# bqcreative_v2.net
KiCad netlist of a schematic drawn in EAGLE
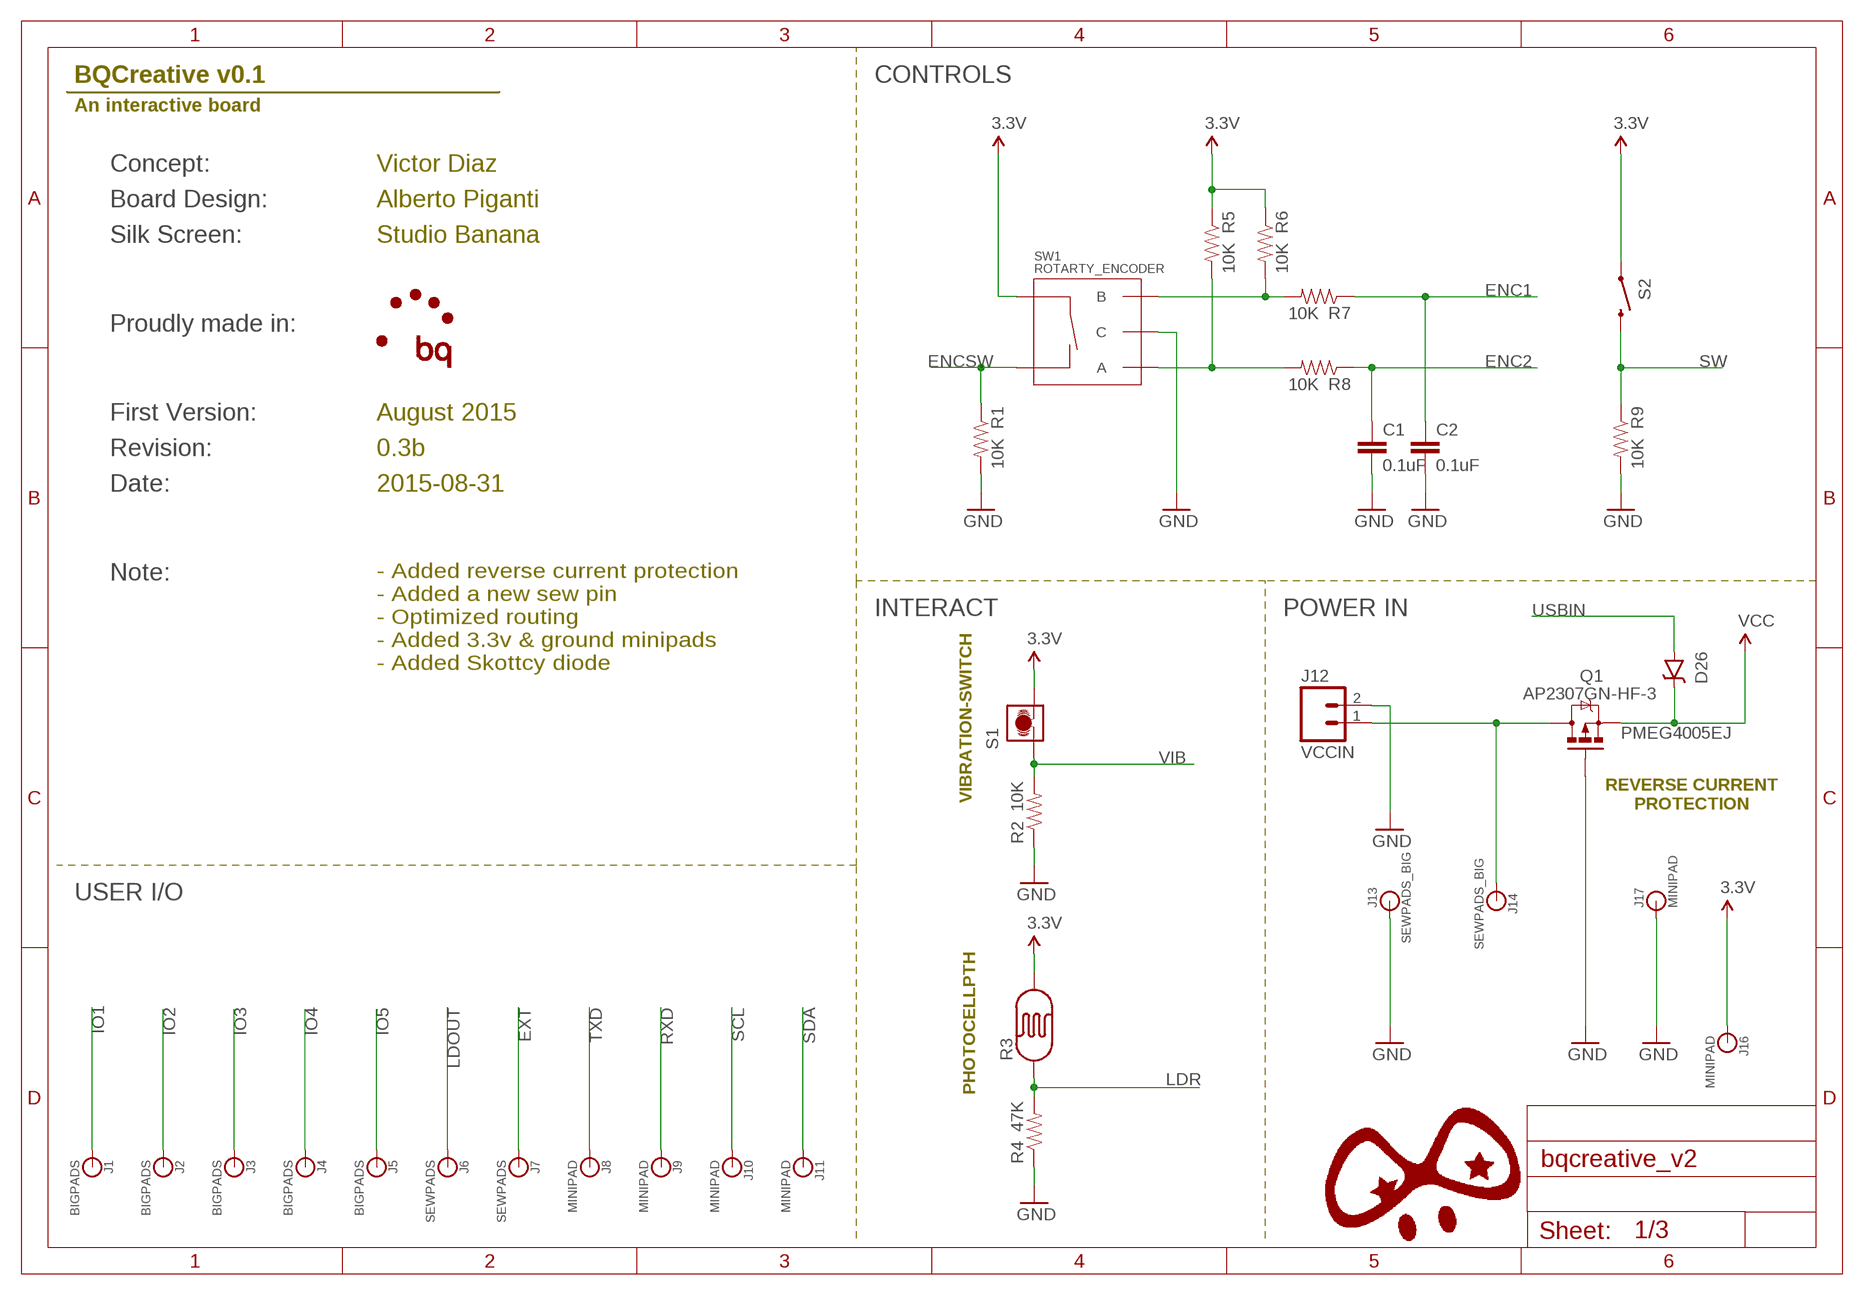
[diagram p0: schematic, sheet 1]
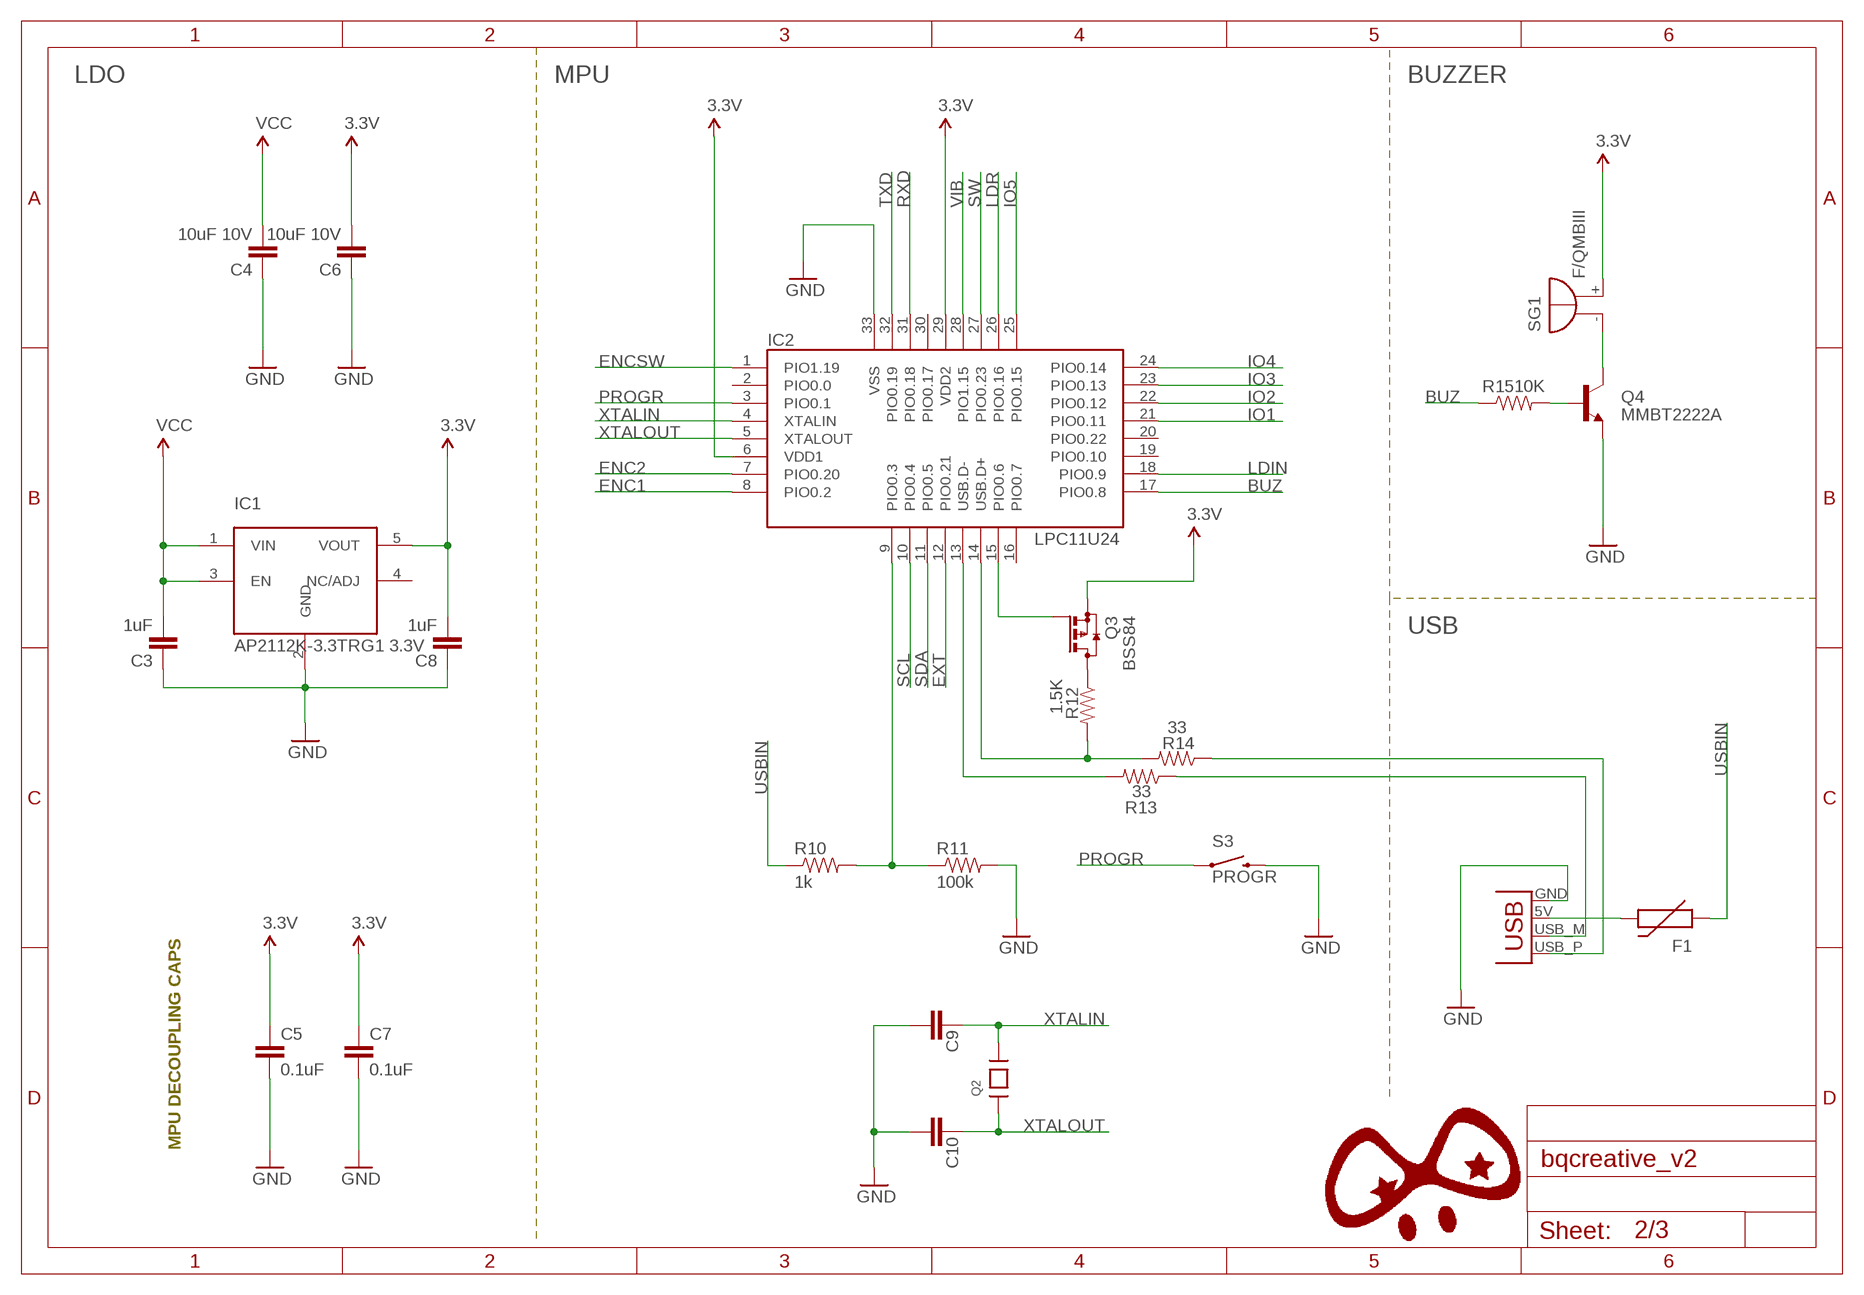
[diagram p1: schematic, sheet 2]
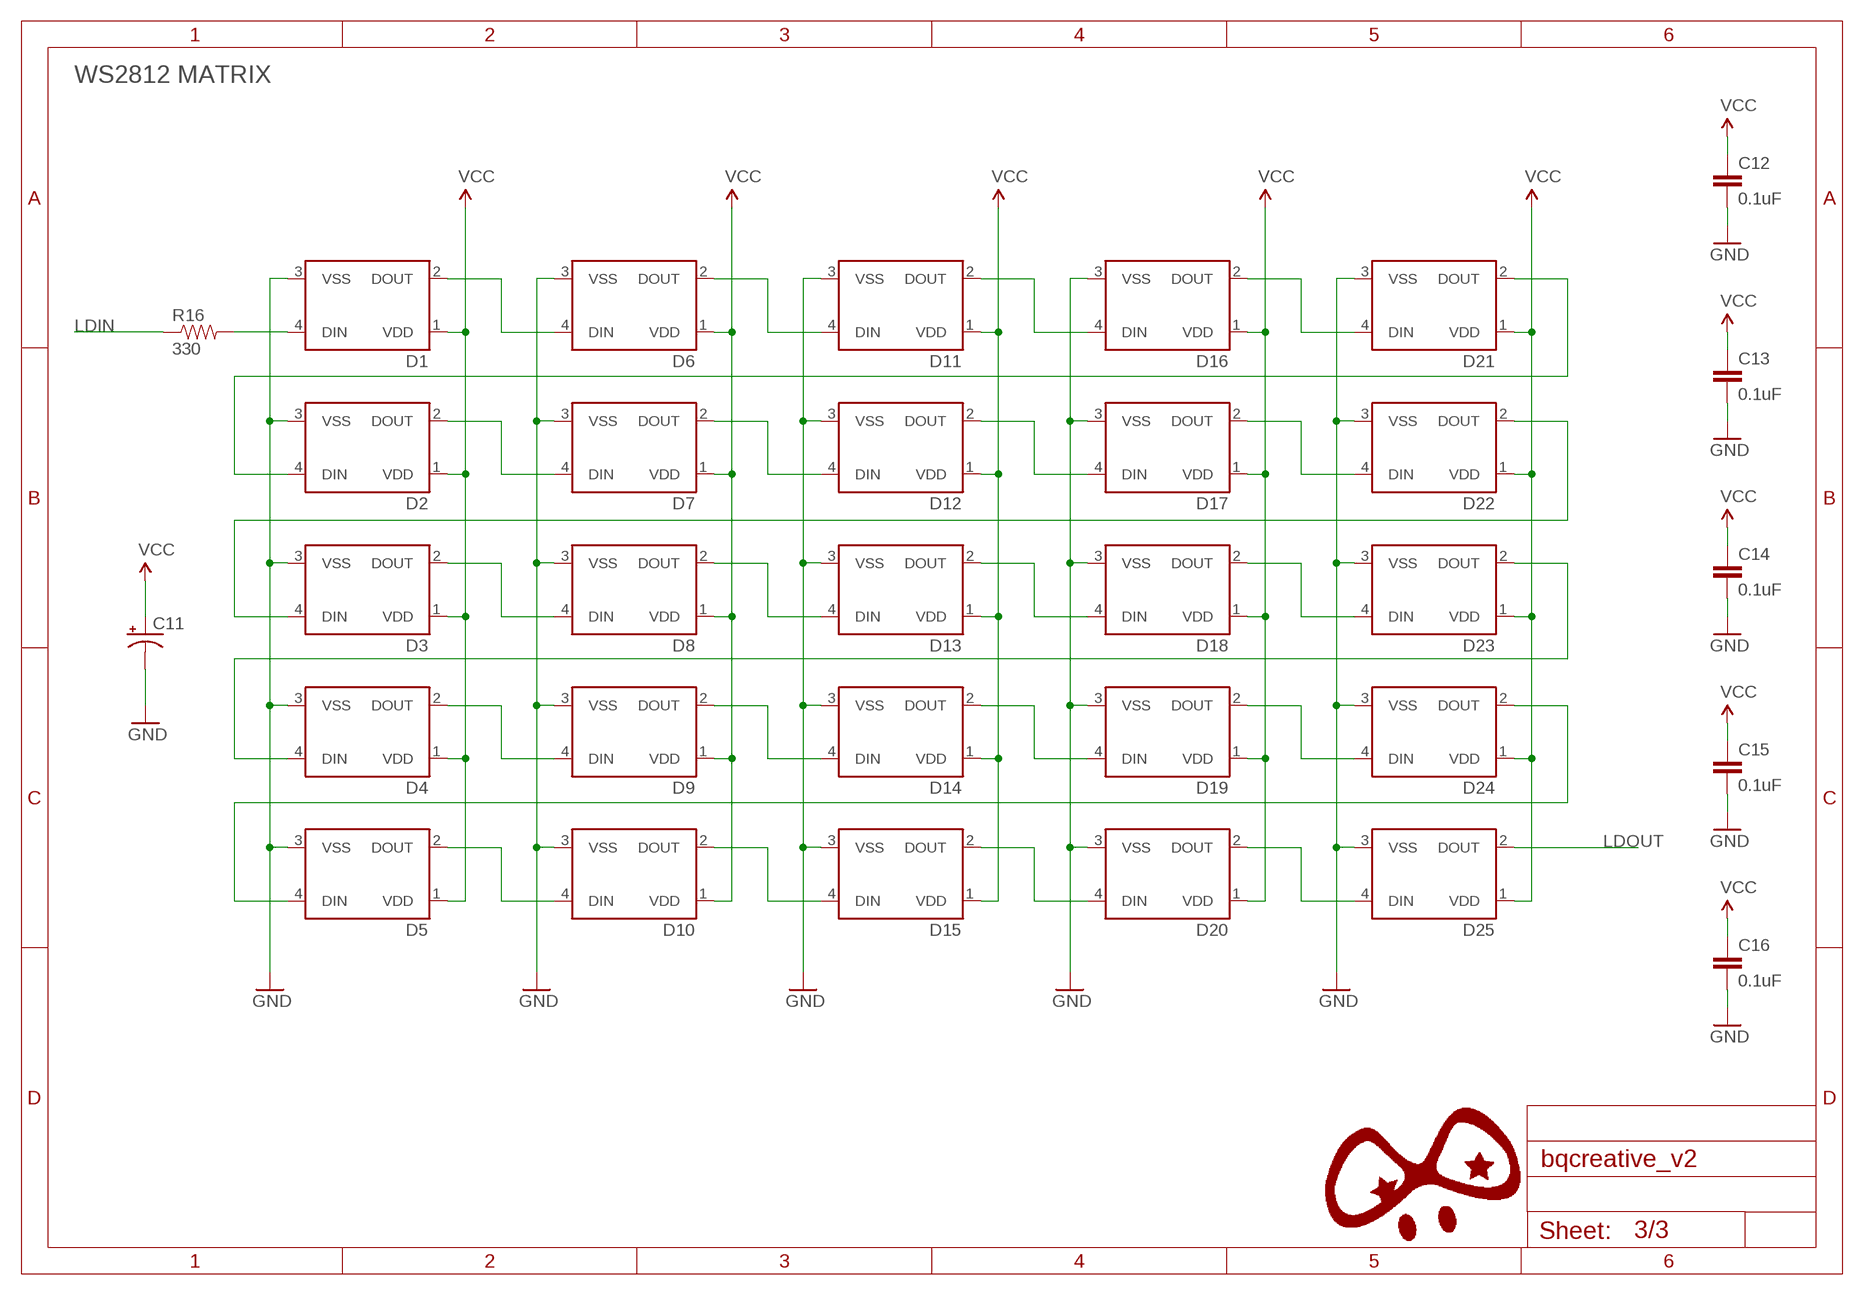
[diagram p2: schematic, sheet 3]

(export (version "E")
  (design (tool "Eeschema 10.0.6"))
  (components
    (comp (ref "C3")
      (value "1uF")
      (footprint "eagle-import:0402-CAP")
      (libsource (lib "eagle-import") (part "SparkFun-Passives_CAP0402-CAP"))
    )
    (comp (ref "C4")
      (value "10uF 10V")
      (footprint "eagle-import:0402-CAP")
      (libsource (lib "eagle-import") (part "SparkFun-Passives_CAP0402-CAP"))
    )
    (comp (ref "C5")
      (value "0.1uF")
      (footprint "eagle-import:0402-CAP")
      (libsource (lib "eagle-import") (part "SparkFun-Passives_CAP0402-CAP"))
    )
    (comp (ref "C6")
      (value "10uF 10V")
      (footprint "eagle-import:0402-CAP")
      (libsource (lib "eagle-import") (part "SparkFun-Passives_CAP0402-CAP"))
    )
    (comp (ref "C7")
      (value "0.1uF")
      (footprint "eagle-import:0402-CAP")
      (libsource (lib "eagle-import") (part "SparkFun-Passives_CAP0402-CAP"))
    )
    (comp (ref "C8")
      (value "1uF")
      (footprint "eagle-import:0402-CAP")
      (libsource (lib "eagle-import") (part "SparkFun-Passives_CAP0402-CAP"))
    )
    (comp (ref "C9")
      (value "27pF")
      (footprint "eagle-import:0402-CAP")
      (libsource (lib "eagle-import") (part "SparkFun-Passives_CAP0402-CAP"))
    )
    (comp (ref "C10")
      (value "27pF")
      (footprint "eagle-import:0402-CAP")
      (libsource (lib "eagle-import") (part "SparkFun-Passives_CAP0402-CAP"))
    )
    (comp (ref "F1")
      (value "PTC0603")
      (footprint "eagle-import:0603")
      (libsource (lib "eagle-import") (part "PTC0603"))
    )
    (comp (ref "IC1")
      (value "AP2112K-3.3TRG1 3.3V")
      (footprint "eagle-import:SOT23-5")
      (libsource (lib "eagle-import") (part "5PIN_REG"))
    )
    (comp (ref "IC2")
      (value "LPC11U24")
      (footprint "eagle-import:HVQFN33_5X5MM")
      (libsource (lib "eagle-import") (part "LPC11U2X_HVQFN33(5X5)"))
    )
    (comp (ref "J15")
      (value "USBPCB")
      (footprint "eagle-import:USB-A-PCB")
      (libsource (lib "eagle-import") (part "USBPCB"))
    )
    (comp (ref "Q2")
      (value "12MHz 4 pad crystal 3.2x2.5")
      (footprint "eagle-import:CRYSTAL_3.2X2.5")
      (libsource (lib "eagle-import") (part "CRYSTAL3.2X2.5"))
    )
    (comp (ref "Q3")
      (value "BSS84")
      (footprint "eagle-import:SOT23")
      (libsource (lib "eagle-import") (part "BSS84"))
    )
    (comp (ref "Q4")
      (value "MMBT2222A")
      (footprint "eagle-import:SOT23-3")
      (libsource (lib "eagle-import") (part "TRANSISTOR_NPNMMBT2222A"))
    )
    (comp (ref "R10")
      (value "1k")
      (footprint "eagle-import:0402-RES")
      (libsource (lib "eagle-import") (part "SparkFun-Passives_RESISTOR0402-RES"))
    )
    (comp (ref "R11")
      (value "100k")
      (footprint "eagle-import:0402-RES")
      (libsource (lib "eagle-import") (part "SparkFun-Passives_RESISTOR0402-RES"))
    )
    (comp (ref "R12")
      (value "1.5K")
      (footprint "eagle-import:0402-RES")
      (libsource (lib "eagle-import") (part "SparkFun-Passives_RESISTOR0402-RES"))
    )
    (comp (ref "R13")
      (value "33")
      (footprint "eagle-import:0402-RES")
      (libsource (lib "eagle-import") (part "SparkFun-Passives_RESISTOR0402-RES"))
    )
    (comp (ref "R14")
      (value "33")
      (footprint "eagle-import:0402-RES")
      (libsource (lib "eagle-import") (part "SparkFun-Passives_RESISTOR0402-RES"))
    )
    (comp (ref "R15")
      (value "10K")
      (footprint "eagle-import:0402-RES")
      (libsource (lib "eagle-import") (part "RESISTOR0402-RES"))
    )
    (comp (ref "S3")
      (value "PROGR")
      (footprint "eagle-import:TACTILE-SWITCH-1101NE")
      (libsource (lib "eagle-import") (part "SWITCH-MOMENTARY-2SMD-1101NE"))
    )
    (comp (ref "SG1")
      (value "F/QMBIII")
      (footprint "eagle-import:F_QMBIII")
      (libsource (lib "eagle-import") (part "F/QMBIII"))
    )
    (comp (ref "C11")
      (value "CAP_POL1206")
      (footprint "eagle-import:EIA3216")
      (libsource (lib "eagle-import") (part "CAP_POL1206"))
    )
    (comp (ref "C12")
      (value "0.1uF")
      (footprint "eagle-import:0402-CAP")
      (libsource (lib "eagle-import") (part "SparkFun-Passives_CAP0402-CAP"))
    )
    (comp (ref "C13")
      (value "0.1uF")
      (footprint "eagle-import:0402-CAP")
      (libsource (lib "eagle-import") (part "SparkFun-Passives_CAP0402-CAP"))
    )
    (comp (ref "C14")
      (value "0.1uF")
      (footprint "eagle-import:0402-CAP")
      (libsource (lib "eagle-import") (part "SparkFun-Passives_CAP0402-CAP"))
    )
    (comp (ref "C15")
      (value "0.1uF")
      (footprint "eagle-import:0402-CAP")
      (libsource (lib "eagle-import") (part "SparkFun-Passives_CAP0402-CAP"))
    )
    (comp (ref "C16")
      (value "0.1uF")
      (footprint "eagle-import:0402-CAP")
      (libsource (lib "eagle-import") (part "SparkFun-Passives_CAP0402-CAP"))
    )
    (comp (ref "D1")
      (value "WS2812B")
      (footprint "eagle-import:WS2812B")
      (libsource (lib "eagle-import") (part "WS2812B"))
    )
    (comp (ref "D2")
      (value "WS2812B")
      (footprint "eagle-import:WS2812B")
      (libsource (lib "eagle-import") (part "WS2812B"))
    )
    (comp (ref "D3")
      (value "WS2812B")
      (footprint "eagle-import:WS2812B")
      (libsource (lib "eagle-import") (part "WS2812B"))
    )
    (comp (ref "D4")
      (value "WS2812B")
      (footprint "eagle-import:WS2812B")
      (libsource (lib "eagle-import") (part "WS2812B"))
    )
    (comp (ref "D5")
      (value "WS2812B")
      (footprint "eagle-import:WS2812B")
      (libsource (lib "eagle-import") (part "WS2812B"))
    )
    (comp (ref "D6")
      (value "WS2812B")
      (footprint "eagle-import:WS2812B")
      (libsource (lib "eagle-import") (part "WS2812B"))
    )
    (comp (ref "D7")
      (value "WS2812B")
      (footprint "eagle-import:WS2812B")
      (libsource (lib "eagle-import") (part "WS2812B"))
    )
    (comp (ref "D8")
      (value "WS2812B")
      (footprint "eagle-import:WS2812B")
      (libsource (lib "eagle-import") (part "WS2812B"))
    )
    (comp (ref "D9")
      (value "WS2812B")
      (footprint "eagle-import:WS2812B")
      (libsource (lib "eagle-import") (part "WS2812B"))
    )
    (comp (ref "D10")
      (value "WS2812B")
      (footprint "eagle-import:WS2812B")
      (libsource (lib "eagle-import") (part "WS2812B"))
    )
    (comp (ref "D11")
      (value "WS2812B")
      (footprint "eagle-import:WS2812B")
      (libsource (lib "eagle-import") (part "WS2812B"))
    )
    (comp (ref "D12")
      (value "WS2812B")
      (footprint "eagle-import:WS2812B")
      (libsource (lib "eagle-import") (part "WS2812B"))
    )
    (comp (ref "D13")
      (value "WS2812B")
      (footprint "eagle-import:WS2812B")
      (libsource (lib "eagle-import") (part "WS2812B"))
    )
    (comp (ref "D14")
      (value "WS2812B")
      (footprint "eagle-import:WS2812B")
      (libsource (lib "eagle-import") (part "WS2812B"))
    )
    (comp (ref "D15")
      (value "WS2812B")
      (footprint "eagle-import:WS2812B")
      (libsource (lib "eagle-import") (part "WS2812B"))
    )
    (comp (ref "D16")
      (value "WS2812B")
      (footprint "eagle-import:WS2812B")
      (libsource (lib "eagle-import") (part "WS2812B"))
    )
    (comp (ref "D17")
      (value "WS2812B")
      (footprint "eagle-import:WS2812B")
      (libsource (lib "eagle-import") (part "WS2812B"))
    )
    (comp (ref "D18")
      (value "WS2812B")
      (footprint "eagle-import:WS2812B")
      (libsource (lib "eagle-import") (part "WS2812B"))
    )
    (comp (ref "D19")
      (value "WS2812B")
      (footprint "eagle-import:WS2812B")
      (libsource (lib "eagle-import") (part "WS2812B"))
    )
    (comp (ref "D20")
      (value "WS2812B")
      (footprint "eagle-import:WS2812B")
      (libsource (lib "eagle-import") (part "WS2812B"))
    )
    (comp (ref "D21")
      (value "WS2812B")
      (footprint "eagle-import:WS2812B")
      (libsource (lib "eagle-import") (part "WS2812B"))
    )
    (comp (ref "D22")
      (value "WS2812B")
      (footprint "eagle-import:WS2812B")
      (libsource (lib "eagle-import") (part "WS2812B"))
    )
    (comp (ref "D23")
      (value "WS2812B")
      (footprint "eagle-import:WS2812B")
      (libsource (lib "eagle-import") (part "WS2812B"))
    )
    (comp (ref "D24")
      (value "WS2812B")
      (footprint "eagle-import:WS2812B")
      (libsource (lib "eagle-import") (part "WS2812B"))
    )
    (comp (ref "D25")
      (value "WS2812B")
      (footprint "eagle-import:WS2812B")
      (libsource (lib "eagle-import") (part "WS2812B"))
    )
    (comp (ref "R16")
      (value "330")
      (footprint "eagle-import:0402-RES")
      (libsource (lib "eagle-import") (part "SparkFun-Passives_RESISTOR0402-RES"))
    )
    (comp (ref "C1")
      (value "0.1uF")
      (footprint "eagle-import:0603-CAP")
      (libsource (lib "eagle-import") (part "CAP0603-CAP"))
    )
    (comp (ref "C2")
      (value "0.1uF")
      (footprint "eagle-import:0603-CAP")
      (libsource (lib "eagle-import") (part "CAP0603-CAP"))
    )
    (comp (ref "D26")
      (value "PMEG4005EJ")
      (footprint "eagle-import:SOD-323")
      (libsource (lib "eagle-import") (part "DIODE-SCHOTTKY-PMEG4005EJ"))
    )
    (comp (ref "J1")
      (value "BIGPADS")
      (footprint "eagle-import:BIGPAD")
      (libsource (lib "eagle-import") (part "BIGPADS"))
    )
    (comp (ref "J2")
      (value "BIGPADS")
      (footprint "eagle-import:BIGPAD")
      (libsource (lib "eagle-import") (part "BIGPADS"))
    )
    (comp (ref "J3")
      (value "BIGPADS")
      (footprint "eagle-import:BIGPAD")
      (libsource (lib "eagle-import") (part "BIGPADS"))
    )
    (comp (ref "J4")
      (value "BIGPADS")
      (footprint "eagle-import:BIGPAD")
      (libsource (lib "eagle-import") (part "BIGPADS"))
    )
    (comp (ref "J5")
      (value "BIGPADS")
      (footprint "eagle-import:BIGPAD")
      (libsource (lib "eagle-import") (part "BIGPADS"))
    )
    (comp (ref "J6")
      (value "SEWPADS")
      (footprint "eagle-import:SEWPAD")
      (libsource (lib "eagle-import") (part "SEWPADS"))
    )
    (comp (ref "J7")
      (value "SEWPADS")
      (footprint "eagle-import:SEWPAD")
      (libsource (lib "eagle-import") (part "SEWPADS"))
    )
    (comp (ref "J8")
      (value "MINIPAD")
      (footprint "eagle-import:MINIPAD")
      (libsource (lib "eagle-import") (part "MINIPAD"))
    )
    (comp (ref "J9")
      (value "MINIPAD")
      (footprint "eagle-import:MINIPAD")
      (libsource (lib "eagle-import") (part "MINIPAD"))
    )
    (comp (ref "J10")
      (value "MINIPAD")
      (footprint "eagle-import:MINIPAD")
      (libsource (lib "eagle-import") (part "MINIPAD"))
    )
    (comp (ref "J11")
      (value "MINIPAD")
      (footprint "eagle-import:MINIPAD")
      (libsource (lib "eagle-import") (part "MINIPAD"))
    )
    (comp (ref "J12")
      (value "VCCIN")
      (footprint "eagle-import:MOLEX-1X2")
      (libsource (lib "eagle-import") (part "M02POLAR"))
    )
    (comp (ref "J13")
      (value "SEWPADS_BIG")
      (footprint "eagle-import:SEWPAD_BIG")
      (libsource (lib "eagle-import") (part "SEWPADS_BIG"))
    )
    (comp (ref "J14")
      (value "SEWPADS_BIG")
      (footprint "eagle-import:SEWPAD_BIG")
      (libsource (lib "eagle-import") (part "SEWPADS_BIG"))
    )
    (comp (ref "J16")
      (value "MINIPAD")
      (footprint "eagle-import:MINIPAD")
      (libsource (lib "eagle-import") (part "MINIPAD"))
    )
    (comp (ref "J17")
      (value "MINIPAD")
      (footprint "eagle-import:MINIPAD")
      (libsource (lib "eagle-import") (part "MINIPAD"))
    )
    (comp (ref "Q1")
      (value "AP2307GN-HF-3")
      (footprint "eagle-import:SOT23-3")
      (libsource (lib "eagle-import") (part "MOSFET-PCHANNEL"))
    )
    (comp (ref "R1")
      (value "10K")
      (footprint "eagle-import:0402-RES")
      (libsource (lib "eagle-import") (part "RESISTOR0402-RES"))
    )
    (comp (ref "R2")
      (value "10K")
      (footprint "eagle-import:0402-RES")
      (libsource (lib "eagle-import") (part "RESISTOR0402-RES"))
    )
    (comp (ref "R3")
      (value "PHOTOCELLPTH")
      (footprint "eagle-import:PHOTOCELL")
      (libsource (lib "eagle-import") (part "PHOTOCELLPTH"))
    )
    (comp (ref "R4")
      (value "47K")
      (footprint "eagle-import:0402-RES")
      (libsource (lib "eagle-import") (part "RESISTOR0402-RES"))
    )
    (comp (ref "R5")
      (value "10K")
      (footprint "eagle-import:0402-RES")
      (libsource (lib "eagle-import") (part "RESISTOR0402-RES"))
    )
    (comp (ref "R6")
      (value "10K")
      (footprint "eagle-import:0402-RES")
      (libsource (lib "eagle-import") (part "RESISTOR0402-RES"))
    )
    (comp (ref "R7")
      (value "10K")
      (footprint "eagle-import:0402-RES")
      (libsource (lib "eagle-import") (part "RESISTOR0402-RES"))
    )
    (comp (ref "R8")
      (value "10K")
      (footprint "eagle-import:0402-RES")
      (libsource (lib "eagle-import") (part "RESISTOR0402-RES"))
    )
    (comp (ref "R9")
      (value "10K")
      (footprint "eagle-import:0402-RES")
      (libsource (lib "eagle-import") (part "RESISTOR0402-RES"))
    )
    (comp (ref "S1")
      (value "VIBRATION-SWITCH")
      (footprint "eagle-import:VIBRATION-SWITCH")
      (libsource (lib "eagle-import") (part "VIBRATION-SWITCH"))
    )
    (comp (ref "S2")
      (value "SWITCH-MOMENTARY-2SMD")
      (footprint "eagle-import:TACTILE-SWITCH-SMD")
      (libsource (lib "eagle-import") (part "SWITCH-MOMENTARY-2SMD"))
    )
    (comp (ref "SW1")
      (value "ROTARTY_ENCODER")
      (footprint "eagle-import:ROTARY_ENC_PLAIN")
      (libsource (lib "eagle-import") (part "ROTARTY_ENCODER"))
    )
  )
  (nets
    (net (code "1") (name "3.3V") (class "Default")
      (node (ref "C5") (pin "1") (pinfunction "1_1") (pintype "passive"))
      (node (ref "C6") (pin "2") (pinfunction "2_2") (pintype "passive"))
      (node (ref "C7") (pin "1") (pinfunction "1_1") (pintype "passive"))
      (node (ref "C8") (pin "2") (pinfunction "2_2") (pintype "passive"))
      (node (ref "IC1") (pin "5") (pinfunction "VOUT_5") (pintype "bidirectional"))
      (node (ref "IC2") (pin "29") (pinfunction "VDD2_29") (pintype "bidirectional"))
      (node (ref "IC2") (pin "6") (pinfunction "VDD1_6") (pintype "bidirectional"))
      (node (ref "J16") (pin "P$1") (pinfunction "1_P$1") (pintype "passive"))
      (node (ref "J16") (pin "P$2") (pinfunction "1_P$2") (pintype "passive"))
      (node (ref "Q3") (pin "2") (pinfunction "S_2") (pintype "passive"))
      (node (ref "R3") (pin "2") (pinfunction "P$2_2") (pintype "bidirectional"))
      (node (ref "R5") (pin "1") (pinfunction "1_1") (pintype "passive"))
      (node (ref "R6") (pin "1") (pinfunction "1_1") (pintype "passive"))
      (node (ref "S1") (pin "2") (pinfunction "2_2") (pintype "passive"))
      (node (ref "S2") (pin "1") (pinfunction "1_1") (pintype "passive"))
      (node (ref "SG1") (pin "+") (pinfunction "-_+") (pintype "passive"))
      (node (ref "SW1") (pin "SW+") (pinfunction "SW+_SW+") (pintype "bidirectional"))
    )
    (net (code "2") (name "BUZ") (class "Default")
      (node (ref "IC2") (pin "17") (pinfunction "PIO0.8_17") (pintype "bidirectional"))
      (node (ref "R15") (pin "1") (pinfunction "1_1") (pintype "passive"))
    )
    (net (code "3") (name "ENC1") (class "Default")
      (node (ref "C2") (pin "1") (pinfunction "1_1") (pintype "passive"))
      (node (ref "IC2") (pin "8") (pinfunction "PIO0.2_8") (pintype "bidirectional"))
      (node (ref "R7") (pin "1") (pinfunction "1_1") (pintype "passive"))
    )
    (net (code "4") (name "ENC2") (class "Default")
      (node (ref "C1") (pin "1") (pinfunction "1_1") (pintype "passive"))
      (node (ref "IC2") (pin "7") (pinfunction "PIO0.20_7") (pintype "bidirectional"))
      (node (ref "R8") (pin "1") (pinfunction "1_1") (pintype "passive"))
    )
    (net (code "5") (name "ENCSW") (class "Default")
      (node (ref "IC2") (pin "1") (pinfunction "PIO1.19_1") (pintype "bidirectional"))
      (node (ref "R1") (pin "1") (pinfunction "1_1") (pintype "passive"))
      (node (ref "SW1") (pin "SW-") (pinfunction "SW-_SW-") (pintype "bidirectional"))
    )
    (net (code "6") (name "EXT") (class "Default")
      (node (ref "IC2") (pin "12") (pinfunction "PIO0.21_12") (pintype "bidirectional"))
      (node (ref "J7") (pin "P$1") (pinfunction "1_P$1") (pintype "passive"))
    )
    (net (code "7") (name "GND") (class "Default")
      (node (ref "C1") (pin "2") (pinfunction "2_2") (pintype "passive"))
      (node (ref "C10") (pin "2") (pinfunction "2_2") (pintype "passive"))
      (node (ref "C11") (pin "C") (pinfunction "-_C") (pintype "passive"))
      (node (ref "C12") (pin "2") (pinfunction "2_2") (pintype "passive"))
      (node (ref "C13") (pin "2") (pinfunction "2_2") (pintype "passive"))
      (node (ref "C14") (pin "2") (pinfunction "2_2") (pintype "passive"))
      (node (ref "C15") (pin "2") (pinfunction "2_2") (pintype "passive"))
      (node (ref "C16") (pin "2") (pinfunction "2_2") (pintype "passive"))
      (node (ref "C2") (pin "2") (pinfunction "2_2") (pintype "passive"))
      (node (ref "C3") (pin "1") (pinfunction "1_1") (pintype "passive"))
      (node (ref "C4") (pin "1") (pinfunction "1_1") (pintype "passive"))
      (node (ref "C5") (pin "2") (pinfunction "2_2") (pintype "passive"))
      (node (ref "C6") (pin "1") (pinfunction "1_1") (pintype "passive"))
      (node (ref "C7") (pin "2") (pinfunction "2_2") (pintype "passive"))
      (node (ref "C8") (pin "1") (pinfunction "1_1") (pintype "passive"))
      (node (ref "C9") (pin "2") (pinfunction "2_2") (pintype "passive"))
      (node (ref "D1") (pin "3") (pinfunction "VSS_3") (pintype "power_in"))
      (node (ref "D10") (pin "3") (pinfunction "VSS_3") (pintype "power_in"))
      (node (ref "D11") (pin "3") (pinfunction "VSS_3") (pintype "power_in"))
      (node (ref "D12") (pin "3") (pinfunction "VSS_3") (pintype "power_in"))
      (node (ref "D13") (pin "3") (pinfunction "VSS_3") (pintype "power_in"))
      (node (ref "D14") (pin "3") (pinfunction "VSS_3") (pintype "power_in"))
      (node (ref "D15") (pin "3") (pinfunction "VSS_3") (pintype "power_in"))
      (node (ref "D16") (pin "3") (pinfunction "VSS_3") (pintype "power_in"))
      (node (ref "D17") (pin "3") (pinfunction "VSS_3") (pintype "power_in"))
      (node (ref "D18") (pin "3") (pinfunction "VSS_3") (pintype "power_in"))
      (node (ref "D19") (pin "3") (pinfunction "VSS_3") (pintype "power_in"))
      (node (ref "D2") (pin "3") (pinfunction "VSS_3") (pintype "power_in"))
      (node (ref "D20") (pin "3") (pinfunction "VSS_3") (pintype "power_in"))
      (node (ref "D21") (pin "3") (pinfunction "VSS_3") (pintype "power_in"))
      (node (ref "D22") (pin "3") (pinfunction "VSS_3") (pintype "power_in"))
      (node (ref "D23") (pin "3") (pinfunction "VSS_3") (pintype "power_in"))
      (node (ref "D24") (pin "3") (pinfunction "VSS_3") (pintype "power_in"))
      (node (ref "D25") (pin "3") (pinfunction "VSS_3") (pintype "power_in"))
      (node (ref "D3") (pin "3") (pinfunction "VSS_3") (pintype "power_in"))
      (node (ref "D4") (pin "3") (pinfunction "VSS_3") (pintype "power_in"))
      (node (ref "D5") (pin "3") (pinfunction "VSS_3") (pintype "power_in"))
      (node (ref "D6") (pin "3") (pinfunction "VSS_3") (pintype "power_in"))
      (node (ref "D7") (pin "3") (pinfunction "VSS_3") (pintype "power_in"))
      (node (ref "D8") (pin "3") (pinfunction "VSS_3") (pintype "power_in"))
      (node (ref "D9") (pin "3") (pinfunction "VSS_3") (pintype "power_in"))
      (node (ref "IC1") (pin "2") (pinfunction "GND_2") (pintype "bidirectional"))
      (node (ref "IC2") (pin "33") (pinfunction "VSS_33") (pintype "bidirectional"))
      (node (ref "J12") (pin "2") (pinfunction "2_2") (pintype "passive"))
      (node (ref "J13") (pin "P$1") (pinfunction "1_P$1") (pintype "passive"))
      (node (ref "J15") (pin "GND") (pinfunction "GND_GND") (pintype "bidirectional"))
      (node (ref "J17") (pin "P$1") (pinfunction "1_P$1") (pintype "passive"))
      (node (ref "J17") (pin "P$2") (pinfunction "1_P$2") (pintype "passive"))
      (node (ref "Q1") (pin "1") (pinfunction "G_1") (pintype "passive"))
      (node (ref "Q4") (pin "2") (pinfunction "E_2") (pintype "passive"))
      (node (ref "R1") (pin "2") (pinfunction "2_2") (pintype "passive"))
      (node (ref "R11") (pin "2") (pinfunction "2_2") (pintype "passive"))
      (node (ref "R2") (pin "1") (pinfunction "1_1") (pintype "passive"))
      (node (ref "R4") (pin "1") (pinfunction "1_1") (pintype "passive"))
      (node (ref "R9") (pin "2") (pinfunction "2_2") (pintype "passive"))
      (node (ref "S3") (pin "2") (pinfunction "2_2") (pintype "passive"))
      (node (ref "SW1") (pin "C") (pinfunction "C_C") (pintype "bidirectional"))
    )
    (net (code "8") (name "IO1") (class "Default")
      (node (ref "IC2") (pin "21") (pinfunction "PIO0.11_21") (pintype "bidirectional"))
      (node (ref "J1") (pin "P$1") (pinfunction "1_P$1") (pintype "passive"))
    )
    (net (code "9") (name "IO2") (class "Default")
      (node (ref "IC2") (pin "22") (pinfunction "PIO0.12_22") (pintype "bidirectional"))
      (node (ref "J2") (pin "P$1") (pinfunction "1_P$1") (pintype "passive"))
    )
    (net (code "10") (name "IO3") (class "Default")
      (node (ref "IC2") (pin "23") (pinfunction "PIO0.13_23") (pintype "bidirectional"))
      (node (ref "J3") (pin "P$1") (pinfunction "1_P$1") (pintype "passive"))
    )
    (net (code "11") (name "IO4") (class "Default")
      (node (ref "IC2") (pin "24") (pinfunction "PIO0.14_24") (pintype "bidirectional"))
      (node (ref "J4") (pin "P$1") (pinfunction "1_P$1") (pintype "passive"))
    )
    (net (code "12") (name "IO5") (class "Default")
      (node (ref "IC2") (pin "25") (pinfunction "PIO0.15_25") (pintype "bidirectional"))
      (node (ref "J5") (pin "P$1") (pinfunction "1_P$1") (pintype "passive"))
    )
    (net (code "13") (name "LDIN") (class "Default")
      (node (ref "IC2") (pin "18") (pinfunction "PIO0.9_18") (pintype "bidirectional"))
      (node (ref "R16") (pin "1") (pinfunction "1_1") (pintype "passive"))
    )
    (net (code "14") (name "LDOUT") (class "Default")
      (node (ref "D25") (pin "2") (pinfunction "DOUT_2") (pintype "output"))
      (node (ref "J6") (pin "P$1") (pinfunction "1_P$1") (pintype "passive"))
    )
    (net (code "15") (name "LDR") (class "Default")
      (node (ref "IC2") (pin "26") (pinfunction "PIO0.16_26") (pintype "bidirectional"))
      (node (ref "R3") (pin "1") (pinfunction "P$1_1") (pintype "bidirectional"))
      (node (ref "R4") (pin "2") (pinfunction "2_2") (pintype "passive"))
    )
    (net (code "16") (name "Net-(D1-DIN)") (class "Default")
      (node (ref "D1") (pin "4") (pinfunction "DIN_4") (pintype "input"))
      (node (ref "R16") (pin "2") (pinfunction "2_2") (pintype "passive"))
    )
    (net (code "17") (name "Net-(D1-DOUT)") (class "Default")
      (node (ref "D1") (pin "2") (pinfunction "DOUT_2") (pintype "output"))
      (node (ref "D6") (pin "4") (pinfunction "DIN_4") (pintype "input"))
    )
    (net (code "18") (name "Net-(D2-DIN)") (class "Default")
      (node (ref "D2") (pin "4") (pinfunction "DIN_4") (pintype "input"))
      (node (ref "D21") (pin "2") (pinfunction "DOUT_2") (pintype "output"))
    )
    (net (code "19") (name "Net-(D2-DOUT)") (class "Default")
      (node (ref "D2") (pin "2") (pinfunction "DOUT_2") (pintype "output"))
      (node (ref "D7") (pin "4") (pinfunction "DIN_4") (pintype "input"))
    )
    (net (code "20") (name "Net-(D3-DOUT)") (class "Default")
      (node (ref "D3") (pin "2") (pinfunction "DOUT_2") (pintype "output"))
      (node (ref "D8") (pin "4") (pinfunction "DIN_4") (pintype "input"))
    )
    (net (code "21") (name "Net-(D4-DOUT)") (class "Default")
      (node (ref "D4") (pin "2") (pinfunction "DOUT_2") (pintype "output"))
      (node (ref "D9") (pin "4") (pinfunction "DIN_4") (pintype "input"))
    )
    (net (code "22") (name "Net-(D10-DIN)") (class "Default")
      (node (ref "D10") (pin "4") (pinfunction "DIN_4") (pintype "input"))
      (node (ref "D5") (pin "2") (pinfunction "DOUT_2") (pintype "output"))
    )
    (net (code "23") (name "Net-(D10-DOUT)") (class "Default")
      (node (ref "D10") (pin "2") (pinfunction "DOUT_2") (pintype "output"))
      (node (ref "D15") (pin "4") (pinfunction "DIN_4") (pintype "input"))
    )
    (net (code "24") (name "Net-(D11-DIN)") (class "Default")
      (node (ref "D11") (pin "4") (pinfunction "DIN_4") (pintype "input"))
      (node (ref "D6") (pin "2") (pinfunction "DOUT_2") (pintype "output"))
    )
    (net (code "25") (name "Net-(D11-DOUT)") (class "Default")
      (node (ref "D11") (pin "2") (pinfunction "DOUT_2") (pintype "output"))
      (node (ref "D16") (pin "4") (pinfunction "DIN_4") (pintype "input"))
    )
    (net (code "26") (name "Net-(D12-DIN)") (class "Default")
      (node (ref "D12") (pin "4") (pinfunction "DIN_4") (pintype "input"))
      (node (ref "D7") (pin "2") (pinfunction "DOUT_2") (pintype "output"))
    )
    (net (code "27") (name "Net-(D12-DOUT)") (class "Default")
      (node (ref "D12") (pin "2") (pinfunction "DOUT_2") (pintype "output"))
      (node (ref "D17") (pin "4") (pinfunction "DIN_4") (pintype "input"))
    )
    (net (code "28") (name "Net-(D13-DIN)") (class "Default")
      (node (ref "D13") (pin "4") (pinfunction "DIN_4") (pintype "input"))
      (node (ref "D8") (pin "2") (pinfunction "DOUT_2") (pintype "output"))
    )
    (net (code "29") (name "Net-(D13-DOUT)") (class "Default")
      (node (ref "D13") (pin "2") (pinfunction "DOUT_2") (pintype "output"))
      (node (ref "D18") (pin "4") (pinfunction "DIN_4") (pintype "input"))
    )
    (net (code "30") (name "Net-(D14-DIN)") (class "Default")
      (node (ref "D14") (pin "4") (pinfunction "DIN_4") (pintype "input"))
      (node (ref "D9") (pin "2") (pinfunction "DOUT_2") (pintype "output"))
    )
    (net (code "31") (name "Net-(D14-DOUT)") (class "Default")
      (node (ref "D14") (pin "2") (pinfunction "DOUT_2") (pintype "output"))
      (node (ref "D19") (pin "4") (pinfunction "DIN_4") (pintype "input"))
    )
    (net (code "32") (name "Net-(D15-DOUT)") (class "Default")
      (node (ref "D15") (pin "2") (pinfunction "DOUT_2") (pintype "output"))
      (node (ref "D20") (pin "4") (pinfunction "DIN_4") (pintype "input"))
    )
    (net (code "33") (name "Net-(D16-DOUT)") (class "Default")
      (node (ref "D16") (pin "2") (pinfunction "DOUT_2") (pintype "output"))
      (node (ref "D21") (pin "4") (pinfunction "DIN_4") (pintype "input"))
    )
    (net (code "34") (name "Net-(D17-DOUT)") (class "Default")
      (node (ref "D17") (pin "2") (pinfunction "DOUT_2") (pintype "output"))
      (node (ref "D22") (pin "4") (pinfunction "DIN_4") (pintype "input"))
    )
    (net (code "35") (name "Net-(D18-DOUT)") (class "Default")
      (node (ref "D18") (pin "2") (pinfunction "DOUT_2") (pintype "output"))
      (node (ref "D23") (pin "4") (pinfunction "DIN_4") (pintype "input"))
    )
    (net (code "36") (name "Net-(D19-DOUT)") (class "Default")
      (node (ref "D19") (pin "2") (pinfunction "DOUT_2") (pintype "output"))
      (node (ref "D24") (pin "4") (pinfunction "DIN_4") (pintype "input"))
    )
    (net (code "37") (name "Net-(D20-DOUT)") (class "Default")
      (node (ref "D20") (pin "2") (pinfunction "DOUT_2") (pintype "output"))
      (node (ref "D25") (pin "4") (pinfunction "DIN_4") (pintype "input"))
    )
    (net (code "38") (name "Net-(D22-DOUT)") (class "Default")
      (node (ref "D22") (pin "2") (pinfunction "DOUT_2") (pintype "output"))
      (node (ref "D3") (pin "4") (pinfunction "DIN_4") (pintype "input"))
    )
    (net (code "39") (name "Net-(D23-DOUT)") (class "Default")
      (node (ref "D23") (pin "2") (pinfunction "DOUT_2") (pintype "output"))
      (node (ref "D4") (pin "4") (pinfunction "DIN_4") (pintype "input"))
    )
    (net (code "40") (name "Net-(D24-DOUT)") (class "Default")
      (node (ref "D24") (pin "2") (pinfunction "DOUT_2") (pintype "output"))
      (node (ref "D5") (pin "4") (pinfunction "DIN_4") (pintype "input"))
    )
    (net (code "41") (name "Net-(IC2-PIO0.3)") (class "Default")
      (node (ref "IC2") (pin "9") (pinfunction "PIO0.3_9") (pintype "bidirectional"))
      (node (ref "R10") (pin "2") (pinfunction "2_2") (pintype "passive"))
      (node (ref "R11") (pin "1") (pinfunction "1_1") (pintype "passive"))
    )
    (net (code "42") (name "Net-(IC2-PIO0.6)") (class "Default")
      (node (ref "IC2") (pin "15") (pinfunction "PIO0.6_15") (pintype "bidirectional"))
      (node (ref "Q3") (pin "1") (pinfunction "G_1") (pintype "passive"))
    )
    (net (code "43") (name "Net-(IC2-USB.D+)") (class "Default")
      (node (ref "IC2") (pin "14") (pinfunction "USB.D+_14") (pintype "bidirectional"))
      (node (ref "R12") (pin "2") (pinfunction "2_2") (pintype "passive"))
      (node (ref "R14") (pin "2") (pinfunction "2_2") (pintype "passive"))
    )
    (net (code "44") (name "Net-(IC2-USB.D-)") (class "Default")
      (node (ref "IC2") (pin "13") (pinfunction "USB.D-_13") (pintype "bidirectional"))
      (node (ref "R13") (pin "2") (pinfunction "2_2") (pintype "passive"))
    )
    (net (code "45") (name "Net-(J14-1)") (class "Default")
      (node (ref "J12") (pin "1") (pinfunction "1_1") (pintype "passive"))
      (node (ref "J14") (pin "P$1") (pinfunction "1_P$1") (pintype "passive"))
      (node (ref "Q1") (pin "3") (pinfunction "D_3") (pintype "passive"))
    )
    (net (code "46") (name "Net-(J15-D+)") (class "Default")
      (node (ref "J15") (pin "USB_P") (pinfunction "D+_USB_P") (pintype "bidirectional"))
      (node (ref "R14") (pin "1") (pinfunction "1_1") (pintype "passive"))
    )
    (net (code "47") (name "Net-(J15-D-)") (class "Default")
      (node (ref "J15") (pin "USB_M") (pinfunction "D-_USB_M") (pintype "bidirectional"))
      (node (ref "R13") (pin "1") (pinfunction "1_1") (pintype "passive"))
    )
    (net (code "48") (name "Net-(J15-VBUS)") (class "Default")
      (node (ref "F1") (pin "2") (pinfunction "2_2") (pintype "bidirectional"))
      (node (ref "J15") (pin "5V") (pinfunction "VBUS_5V") (pintype "bidirectional"))
    )
    (net (code "49") (name "Net-(Q3-D)") (class "Default")
      (node (ref "Q3") (pin "3") (pinfunction "D_3") (pintype "passive"))
      (node (ref "R12") (pin "1") (pinfunction "1_1") (pintype "passive"))
    )
    (net (code "50") (name "Net-(Q4-B)") (class "Default")
      (node (ref "Q4") (pin "1") (pinfunction "B_1") (pintype "passive"))
      (node (ref "R15") (pin "2") (pinfunction "2_2") (pintype "passive"))
    )
    (net (code "51") (name "Net-(Q4-C)") (class "Default")
      (node (ref "Q4") (pin "3") (pinfunction "C_3") (pintype "passive"))
      (node (ref "SG1") (pin "-") (pinfunction "+_-") (pintype "passive"))
    )
    (net (code "52") (name "Net-(R5-Pad2)") (class "Default")
      (node (ref "R5") (pin "2") (pinfunction "2_2") (pintype "passive"))
      (node (ref "R8") (pin "2") (pinfunction "2_2") (pintype "passive"))
      (node (ref "SW1") (pin "A") (pinfunction "A_A") (pintype "bidirectional"))
    )
    (net (code "53") (name "Net-(R6-Pad2)") (class "Default")
      (node (ref "R6") (pin "2") (pinfunction "2_2") (pintype "passive"))
      (node (ref "R7") (pin "2") (pinfunction "2_2") (pintype "passive"))
      (node (ref "SW1") (pin "B") (pinfunction "B_B") (pintype "bidirectional"))
    )
    (net (code "54") (name "PROGR") (class "Default")
      (node (ref "IC2") (pin "3") (pinfunction "PIO0.1_3") (pintype "bidirectional"))
      (node (ref "S3") (pin "1") (pinfunction "1_1") (pintype "passive"))
    )
    (net (code "55") (name "RXD") (class "Default")
      (node (ref "IC2") (pin "31") (pinfunction "PIO0.18_31") (pintype "bidirectional"))
      (node (ref "J9") (pin "P$1") (pinfunction "1_P$1") (pintype "passive"))
      (node (ref "J9") (pin "P$2") (pinfunction "1_P$2") (pintype "passive"))
    )
    (net (code "56") (name "SCL") (class "Default")
      (node (ref "IC2") (pin "10") (pinfunction "PIO0.4_10") (pintype "bidirectional"))
      (node (ref "J10") (pin "P$1") (pinfunction "1_P$1") (pintype "passive"))
      (node (ref "J10") (pin "P$2") (pinfunction "1_P$2") (pintype "passive"))
    )
    (net (code "57") (name "SDA") (class "Default")
      (node (ref "IC2") (pin "11") (pinfunction "PIO0.5_11") (pintype "bidirectional"))
      (node (ref "J11") (pin "P$1") (pinfunction "1_P$1") (pintype "passive"))
      (node (ref "J11") (pin "P$2") (pinfunction "1_P$2") (pintype "passive"))
    )
    (net (code "58") (name "SW") (class "Default")
      (node (ref "IC2") (pin "27") (pinfunction "PIO0.23_27") (pintype "bidirectional"))
      (node (ref "R9") (pin "1") (pinfunction "1_1") (pintype "passive"))
      (node (ref "S2") (pin "3") (pinfunction "2_3") (pintype "passive"))
    )
    (net (code "59") (name "TXD") (class "Default")
      (node (ref "IC2") (pin "32") (pinfunction "PIO0.19_32") (pintype "bidirectional"))
      (node (ref "J8") (pin "P$1") (pinfunction "1_P$1") (pintype "passive"))
      (node (ref "J8") (pin "P$2") (pinfunction "1_P$2") (pintype "passive"))
    )
    (net (code "60") (name "USBIN") (class "Default")
      (node (ref "D26") (pin "A") (pinfunction "A_A") (pintype "passive"))
      (node (ref "F1") (pin "1") (pinfunction "1_1") (pintype "bidirectional"))
      (node (ref "R10") (pin "1") (pinfunction "1_1") (pintype "passive"))
    )
    (net (code "61") (name "VCC") (class "Default")
      (node (ref "C11") (pin "A") (pinfunction "+_A") (pintype "passive"))
      (node (ref "C12") (pin "1") (pinfunction "1_1") (pintype "passive"))
      (node (ref "C13") (pin "1") (pinfunction "1_1") (pintype "passive"))
      (node (ref "C14") (pin "1") (pinfunction "1_1") (pintype "passive"))
      (node (ref "C15") (pin "1") (pinfunction "1_1") (pintype "passive"))
      (node (ref "C16") (pin "1") (pinfunction "1_1") (pintype "passive"))
      (node (ref "C3") (pin "2") (pinfunction "2_2") (pintype "passive"))
      (node (ref "C4") (pin "2") (pinfunction "2_2") (pintype "passive"))
      (node (ref "D1") (pin "1") (pinfunction "VDD_1") (pintype "power_in"))
      (node (ref "D10") (pin "1") (pinfunction "VDD_1") (pintype "power_in"))
      (node (ref "D11") (pin "1") (pinfunction "VDD_1") (pintype "power_in"))
      (node (ref "D12") (pin "1") (pinfunction "VDD_1") (pintype "power_in"))
      (node (ref "D13") (pin "1") (pinfunction "VDD_1") (pintype "power_in"))
      (node (ref "D14") (pin "1") (pinfunction "VDD_1") (pintype "power_in"))
      (node (ref "D15") (pin "1") (pinfunction "VDD_1") (pintype "power_in"))
      (node (ref "D16") (pin "1") (pinfunction "VDD_1") (pintype "power_in"))
      (node (ref "D17") (pin "1") (pinfunction "VDD_1") (pintype "power_in"))
      (node (ref "D18") (pin "1") (pinfunction "VDD_1") (pintype "power_in"))
      (node (ref "D19") (pin "1") (pinfunction "VDD_1") (pintype "power_in"))
      (node (ref "D2") (pin "1") (pinfunction "VDD_1") (pintype "power_in"))
      (node (ref "D20") (pin "1") (pinfunction "VDD_1") (pintype "power_in"))
      (node (ref "D21") (pin "1") (pinfunction "VDD_1") (pintype "power_in"))
      (node (ref "D22") (pin "1") (pinfunction "VDD_1") (pintype "power_in"))
      (node (ref "D23") (pin "1") (pinfunction "VDD_1") (pintype "power_in"))
      (node (ref "D24") (pin "1") (pinfunction "VDD_1") (pintype "power_in"))
      (node (ref "D25") (pin "1") (pinfunction "VDD_1") (pintype "power_in"))
      (node (ref "D26") (pin "C") (pinfunction "C_C") (pintype "passive"))
      (node (ref "D3") (pin "1") (pinfunction "VDD_1") (pintype "power_in"))
      (node (ref "D4") (pin "1") (pinfunction "VDD_1") (pintype "power_in"))
      (node (ref "D5") (pin "1") (pinfunction "VDD_1") (pintype "power_in"))
      (node (ref "D6") (pin "1") (pinfunction "VDD_1") (pintype "power_in"))
      (node (ref "D7") (pin "1") (pinfunction "VDD_1") (pintype "power_in"))
      (node (ref "D8") (pin "1") (pinfunction "VDD_1") (pintype "power_in"))
      (node (ref "D9") (pin "1") (pinfunction "VDD_1") (pintype "power_in"))
      (node (ref "IC1") (pin "1") (pinfunction "VIN_1") (pintype "bidirectional"))
      (node (ref "IC1") (pin "3") (pinfunction "EN_3") (pintype "bidirectional"))
      (node (ref "Q1") (pin "2") (pinfunction "S_2") (pintype "passive"))
    )
    (net (code "62") (name "VIB") (class "Default")
      (node (ref "IC2") (pin "28") (pinfunction "PIO1.15_28") (pintype "bidirectional"))
      (node (ref "R2") (pin "2") (pinfunction "2_2") (pintype "passive"))
      (node (ref "S1") (pin "1") (pinfunction "1_1") (pintype "passive"))
    )
    (net (code "63") (name "XTALIN") (class "Default")
      (node (ref "C9") (pin "1") (pinfunction "1_1") (pintype "passive"))
      (node (ref "IC2") (pin "4") (pinfunction "XTALIN_4") (pintype "bidirectional"))
      (node (ref "Q2") (pin "3") (pinfunction "P$2_3") (pintype "passive"))
    )
    (net (code "64") (name "XTALOUT") (class "Default")
      (node (ref "C10") (pin "1") (pinfunction "1_1") (pintype "passive"))
      (node (ref "IC2") (pin "5") (pinfunction "XTALOUT_5") (pintype "bidirectional"))
      (node (ref "Q2") (pin "1") (pinfunction "P$1_1") (pintype "passive"))
    )
    (net (code "65") (name "unconnected-(IC1-NC{slash}ADJ-Pad4)") (class "Default")
      (node (ref "IC1") (pin "4") (pinfunction "NC/ADJ_4") (pintype "bidirectional"))
    )
    (net (code "66") (name "unconnected-(IC2-PIO0.0-Pad2)") (class "Default")
      (node (ref "IC2") (pin "2") (pinfunction "PIO0.0_2") (pintype "bidirectional"))
    )
    (net (code "67") (name "unconnected-(IC2-PIO0.7-Pad16)") (class "Default")
      (node (ref "IC2") (pin "16") (pinfunction "PIO0.7_16") (pintype "bidirectional"))
    )
    (net (code "68") (name "unconnected-(IC2-PIO0.10-Pad19)") (class "Default")
      (node (ref "IC2") (pin "19") (pinfunction "PIO0.10_19") (pintype "bidirectional"))
    )
    (net (code "69") (name "unconnected-(IC2-PIO0.17-Pad30)") (class "Default")
      (node (ref "IC2") (pin "30") (pinfunction "PIO0.17_30") (pintype "bidirectional"))
    )
    (net (code "70") (name "unconnected-(IC2-PIO0.22-Pad20)") (class "Default")
      (node (ref "IC2") (pin "20") (pinfunction "PIO0.22_20") (pintype "bidirectional"))
    )
  )
)
